# ARM_VRD240512MP-8W.net
KiCad netlist of a schematic drawn in Altium Designer
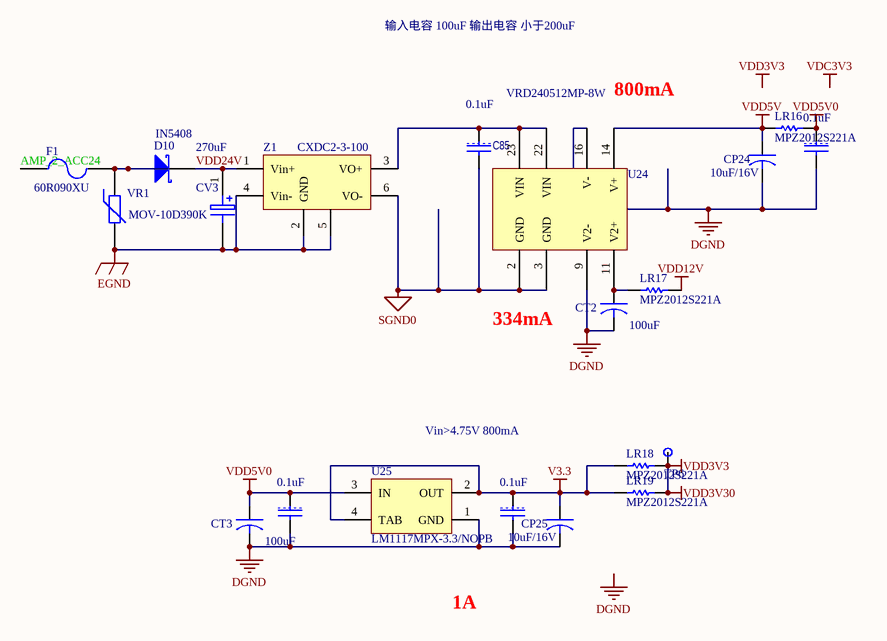
[diagram p0: 电源ARM_VRD240512MP-8W.SchDoc]

(export (version "E")
  (design (tool "Eeschema 10.0.6"))
  (components
    (comp (ref "C85")
      (value "0.1uF")
      (footprint "1608[0603]C")
      (description "多层陶瓷电容器MLCC - SMD/SMT 0603 0.1uF 50volts X7R 10%")
      (fields (field (name "MANUFACTURER") "TDK") (field (name "MANUFACTURER PART NUMBER") "C1608X7R1H104K"))
      (libsource (lib "*") (part "CAP"))
    )
    (comp (ref "C86")
      (value "0.1uF")
      (footprint "1608[0603]C")
      (description "多层陶瓷电容器MLCC - SMD/SMT 0603 0.1uF 50volts X7R 10%")
      (fields (field (name "MANUFACTURER") "TDK") (field (name "MANUFACTURER PART NUMBER") "C1608X7R1H104K"))
      (libsource (lib "*") (part "CAP"))
    )
    (comp (ref "C87")
      (value "0.1uF")
      (footprint "1608[0603]C")
      (description "多层陶瓷电容器MLCC - SMD/SMT 0603 0.1uF 50volts X7R 10%")
      (fields (field (name "MANUFACTURER") "TDK") (field (name "MANUFACTURER PART NUMBER") "C1608X7R1H104K"))
      (libsource (lib "*") (part "CAP"))
    )
    (comp (ref "C88")
      (value "0.1uF")
      (footprint "1608[0603]C")
      (description "多层陶瓷电容器MLCC - SMD/SMT 0603 0.1uF 50volts X7R 10%")
      (fields (field (name "MANUFACTURER") "TDK") (field (name "MANUFACTURER PART NUMBER") "C1608X7R1H104K"))
      (libsource (lib "*") (part "CAP"))
    )
    (comp (ref "CP24")
      (value "10uF/16V")
      (footprint "3216[1206]CB")
      (description "Tantalum Capacitor")
      (libsource (lib "*") (part "CAPACITOR"))
    )
    (comp (ref "CP25")
      (value "10uF/16V")
      (footprint "3216[1206]CB")
      (description "Tantalum Capacitor")
      (libsource (lib "*") (part "CAPACITOR"))
    )
    (comp (ref "CT2")
      (value "100uF")
      (footprint "6032[2312]CC")
      (description "钽质电容器-固体SMD 16V 100uF 10%")
      (fields (field (name "MANUFACTURER") "AVX") (field (name "MANUFACTURER PART NUMBER") "TAJC107K016RNJ"))
      (libsource (lib "*") (part "CAPACITOR"))
    )
    (comp (ref "CT3")
      (value "100uF")
      (footprint "6032[2312]CC")
      (description "钽质电容器-固体SMD 16V 100uF 10%")
      (fields (field (name "MANUFACTURER") "AVX") (field (name "MANUFACTURER PART NUMBER") "TAJC107K016RNJ"))
      (libsource (lib "*") (part "CAPACITOR"))
    )
    (comp (ref "CV3")
      (value "270uF")
      (footprint "CAPPR5-10x20/H1.1")
      (description "插针 铝质电解电容器 - 带引线 270UF 50V ELECT FM RADIAL")
      (fields
        (field (name "MANUFACTURER") "Panasonic Electronic Components")
        (field (name "MANUFACTURER PART NUMBER") "EEU-FM1H271")
      )
      (libsource (lib "*") (part "ELECTRO1"))
    )
    (comp (ref "D10")
      (value "IN5408")
      (footprint "DO-214AB/SMC")
      (description "肖特基二极管与整流器 3.0 Amp 60 Volt")
      (fields
        (field (name "MANUFACTURER") "Vishay Semiconductors")
        (field (name "MANUFACTURER PART NUMBER") "SS36-E3/57T")
      )
      (libsource (lib "Miscellaneous Devices") (part "D Schottky"))
    )
    (comp (ref "F1")
      (value "60R090XU")
      (footprint "FUS-0.2")
      (description "插针 可复位保险丝 60V POLYFUSE .100A RADIAL LEADS")
      (fields (field (name "MANUFACTURER") "Littelfuse") (field (name "MANUFACTURER PART NUMBER") "60R010XU"))
      (libsource (lib "Miscellaneous Devices") (part "Fuse 2"))
    )
    (comp (ref "LR16")
      (value "MPZ2012S221A")
      (footprint "2012[0805]")
      (description "电磁干扰滤波珠子、扼流圈和阵列 Ferrite Chip Beads")
      (fields (field (name "MANUFACTURER") "TDK"))
      (libsource (lib "Miscellaneous Devices") (part "Res Semi"))
    )
    (comp (ref "LR17")
      (value "MPZ2012S221A")
      (footprint "2012[0805]")
      (description "电磁干扰滤波珠子、扼流圈和阵列 Ferrite Chip Beads")
      (fields (field (name "MANUFACTURER") "TDK"))
      (libsource (lib "Miscellaneous Devices") (part "Res Semi"))
    )
    (comp (ref "LR18")
      (value "MPZ2012S221A")
      (footprint "2012[0805]")
      (description "电磁干扰滤波珠子、扼流圈和阵列 Ferrite Chip Beads")
      (fields (field (name "MANUFACTURER") "TDK"))
      (libsource (lib "Miscellaneous Devices") (part "Res Semi"))
    )
    (comp (ref "LR19")
      (value "MPZ2012S221A")
      (footprint "2012[0805]")
      (description "电磁干扰滤波珠子、扼流圈和阵列 Ferrite Chip Beads")
      (fields (field (name "MANUFACTURER") "TDK"))
      (libsource (lib "Miscellaneous Devices") (part "Res Semi"))
    )
    (comp (ref "TP6")
      (value "TP")
      (footprint "TP")
      (description "Test Point")
      (libsource (lib "S3C2440V9") (part "Test Point"))
    )
    (comp (ref "U24")
      (value "VRD240512MP-8W")
      (footprint "DIP-7(24)W")
      (description "插针VRD240512MP-8W 2:1 1500V 82%")
      (libsource (lib "一体机V5") (part "VRD240512MP-8W"))
    )
    (comp (ref "U25")
      (value "LM1117MPX-3.3/NOPB")
      (footprint "MP04A_N")
      (description "800mA Low-Dropout Linear Regulator, 4-pin SOT-223, Pb-Free")
      (fields
        (field (name "MANUFACTURER") "National Semiconductor")
        (field (name "PUBLISHER") "Altium Limited")
      )
      (libsource (lib "NSC LDO") (part "LM1117MPX-3.3/NOPB"))
    )
    (comp (ref "VR1")
      (value "MOV-10D390K")
      (footprint "RAD-0.3")
      (description "插针 压敏电阻 500A 39volts 10%")
      (fields (field (name "MANUFACTURER") "Bourns"))
      (libsource (lib "Miscellaneous Devices") (part "Res Varistor"))
    )
    (comp (ref "Z1")
      (value "CXDC2-3-100")
      (footprint "DIP-6(20)W")
      (description "插针 Filter")
      (libsource (lib "altium-import") (part "root_0_CXDB_"))
    )
  )
  (nets
    (net (code "1") (name "/AMP_2_ACC24") (class "Default")
      (node (ref "F1") (pin "1") (pinfunction "1_1") (pintype "passive"))
    )
    (net (code "2") (name "/VDD24V") (class "Default")
      (node (ref "CV3") (pin "1") (pinfunction "1_1") (pintype "passive"))
      (node (ref "D10") (pin "2") (pinfunction "K_2") (pintype "passive"))
      (node (ref "Z1") (pin "1") (pinfunction "Vin+_1") (pintype "passive"))
    )
    (net (code "3") (name "DGND") (class "Default")
      (node (ref "C86") (pin "2") (pinfunction "2_2") (pintype "passive"))
      (node (ref "C87") (pin "2") (pinfunction "2_2") (pintype "passive"))
      (node (ref "C88") (pin "2") (pinfunction "2_2") (pintype "passive"))
      (node (ref "CP24") (pin "2") (pinfunction "2_2") (pintype "passive"))
      (node (ref "CP25") (pin "2") (pinfunction "2_2") (pintype "passive"))
      (node (ref "CT2") (pin "2") (pinfunction "2_2") (pintype "passive"))
      (node (ref "CT3") (pin "2") (pinfunction "2_2") (pintype "passive"))
      (node (ref "U24") (pin "16") (pinfunction "V-_16") (pintype "passive"))
      (node (ref "U24") (pin "9") (pinfunction "V2-_9") (pintype "passive"))
      (node (ref "U25") (pin "1") (pinfunction "GND_1") (pintype "power_in"))
    )
    (net (code "4") (name "EGND") (class "Default")
      (node (ref "CV3") (pin "2") (pinfunction "2_2") (pintype "passive"))
      (node (ref "VR1") (pin "2") (pinfunction "2_2") (pintype "passive"))
      (node (ref "Z1") (pin "2") (pinfunction "GND_2") (pintype "passive"))
      (node (ref "Z1") (pin "4") (pinfunction "Vin-_4") (pintype "passive"))
      (node (ref "Z1") (pin "5") (pinfunction "GND_5") (pintype "passive"))
    )
    (net (code "5") (name "Net-(D10-A)") (class "Default")
      (node (ref "D10") (pin "1") (pinfunction "A_1") (pintype "passive"))
      (node (ref "F1") (pin "2") (pinfunction "2_2") (pintype "passive"))
      (node (ref "VR1") (pin "1") (pinfunction "1_1") (pintype "passive"))
    )
    (net (code "6") (name "Net-(U24-V2+)") (class "Default")
      (node (ref "CT2") (pin "1") (pinfunction "1_1") (pintype "passive"))
      (node (ref "LR17") (pin "1") (pinfunction "1_1") (pintype "passive"))
      (node (ref "U24") (pin "11") (pinfunction "V2+_11") (pintype "passive"))
    )
    (net (code "7") (name "Net-(Z1-VO+)") (class "Default")
      (node (ref "C85") (pin "1") (pinfunction "1_1") (pintype "passive"))
      (node (ref "U24") (pin "22") (pinfunction "VIN_22") (pintype "passive"))
      (node (ref "U24") (pin "23") (pinfunction "VIN_23") (pintype "passive"))
      (node (ref "Z1") (pin "3") (pinfunction "VO+_3") (pintype "passive"))
    )
    (net (code "8") (name "SGND0") (class "Default")
      (node (ref "C85") (pin "2") (pinfunction "2_2") (pintype "passive"))
      (node (ref "U24") (pin "2") (pinfunction "GND_2") (pintype "passive"))
      (node (ref "U24") (pin "3") (pinfunction "GND_3") (pintype "passive"))
      (node (ref "Z1") (pin "6") (pinfunction "VO-_6") (pintype "passive"))
    )
    (net (code "9") (name "V3.3") (class "Default")
      (node (ref "C88") (pin "1") (pinfunction "1_1") (pintype "passive"))
      (node (ref "CP25") (pin "1") (pinfunction "1_1") (pintype "passive"))
      (node (ref "LR18") (pin "1") (pinfunction "1_1") (pintype "passive"))
      (node (ref "LR19") (pin "1") (pinfunction "1_1") (pintype "passive"))
      (node (ref "U25") (pin "2") (pinfunction "OUT_2") (pintype "power_in"))
      (node (ref "U25") (pin "4") (pinfunction "TAB_4") (pintype "power_in"))
    )
    (net (code "11") (name "VDD3V3") (class "Default")
      (node (ref "LR18") (pin "2") (pinfunction "2_2") (pintype "passive"))
      (node (ref "LR19") (pin "2") (pinfunction "2_2") (pintype "passive"))
      (node (ref "TP6") (pin "1") (pinfunction "TestPoint_1") (pintype "passive"))
    )
    (net (code "12") (name "VDD5V") (class "Default")
      (node (ref "CP24") (pin "1") (pinfunction "1_1") (pintype "passive"))
      (node (ref "LR16") (pin "1") (pinfunction "1_1") (pintype "passive"))
      (node (ref "U24") (pin "14") (pinfunction "V+_14") (pintype "passive"))
    )
    (net (code "13") (name "VDD5V0") (class "Default")
      (node (ref "C86") (pin "1") (pinfunction "1_1") (pintype "passive"))
      (node (ref "C87") (pin "1") (pinfunction "1_1") (pintype "passive"))
      (node (ref "CT3") (pin "1") (pinfunction "1_1") (pintype "passive"))
      (node (ref "LR16") (pin "2") (pinfunction "2_2") (pintype "passive"))
      (node (ref "U25") (pin "3") (pinfunction "IN_3") (pintype "power_in"))
    )
    (net (code "14") (name "VDD12V") (class "Default")
      (node (ref "LR17") (pin "2") (pinfunction "2_2") (pintype "passive"))
    )
  )
)
